# HelloLED.net
KiCad netlist of a schematic drawn in EAGLE
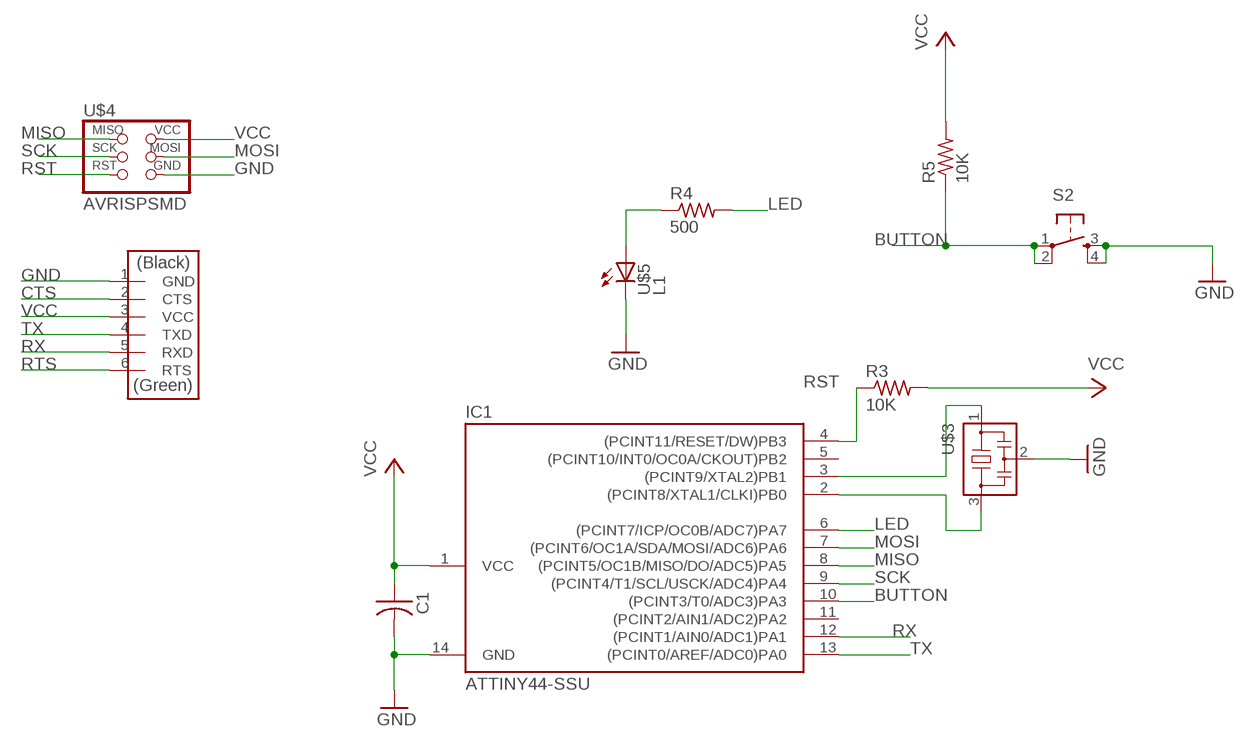
[diagram p0: schematic, sheet 1]

(export (version "E")
  (design (tool "Eeschema 10.0.6"))
  (components
    (comp (ref "C1")
      (value "CAP-US1206FAB")
      (footprint "eagle-import:C1206FAB")
      (libsource (lib "eagle-import") (part "CAP-US1206FAB"))
    )
    (comp (ref "IC1")
      (value "ATTINY44-SSU")
      (footprint "eagle-import:SOIC14")
      (libsource (lib "eagle-import") (part "ATTINY44-SSU"))
    )
    (comp (ref "R3")
      (value "10K")
      (footprint "eagle-import:R1206FAB")
      (fields (field (name "MF") "AVX CORPORATION") (field (name "MPN") "12106D226KAT2A"))
      (libsource (lib "eagle-import") (part "RES-US1206FAB"))
    )
    (comp (ref "R4")
      (value "500")
      (footprint "eagle-import:R1206FAB")
      (libsource (lib "eagle-import") (part "RES-US1206FAB"))
    )
    (comp (ref "R5")
      (value "10K")
      (footprint "eagle-import:R1206FAB")
      (fields (field (name "MF") "AVX CORPORATION") (field (name "MPN") "12106D226KAT2A"))
      (libsource (lib "eagle-import") (part "RES-US1206FAB"))
    )
    (comp (ref "S2")
      (value "6MM_SWITCH6MM_SWITCH")
      (footprint "eagle-import:6MM_SWITCH")
      (libsource (lib "eagle-import") (part "6MM_SWITCH6MM_SWITCH"))
    )
    (comp (ref "U$1")
      (value "FTDI-SMD-HEADER")
      (footprint "eagle-import:1X06SMD")
      (libsource (lib "eagle-import") (part "FTDI-SMD-HEADER"))
    )
    (comp (ref "U$3")
      (value "RESONATOR")
      (footprint "eagle-import:EFOBM")
      (libsource (lib "eagle-import") (part "RESONATOR"))
    )
    (comp (ref "U$4")
      (value "AVRISPSMD")
      (footprint "eagle-import:2X03SMD")
      (libsource (lib "eagle-import") (part "AVRISPSMD"))
    )
    (comp (ref "U$5")
      (value "L1")
      (footprint "eagle-import:LED1206FAB")
      (libsource (lib "eagle-import") (part "LEDFAB1206"))
    )
  )
  (nets
    (net (code "1") (name "/BUTTON") (class "Default")
      (node (ref "IC1") (pin "10") (pinfunction "(PCINT3/T0/ADC3)PA3_10") (pintype "bidirectional"))
      (node (ref "R5") (pin "1") (pinfunction "1_1") (pintype "passive"))
      (node (ref "S2") (pin "1") (pinfunction "P_1") (pintype "passive"))
      (node (ref "S2") (pin "2") (pinfunction "P1_2") (pintype "passive"))
    )
    (net (code "2") (name "/CTS") (class "Default")
      (node (ref "U$1") (pin "2") (pinfunction "CTS_2") (pintype "bidirectional"))
    )
    (net (code "3") (name "/LED") (class "Default")
      (node (ref "IC1") (pin "6") (pinfunction "(PCINT7/ICP/OC0B/ADC7)PA7_6") (pintype "bidirectional"))
      (node (ref "R4") (pin "2") (pinfunction "2_2") (pintype "passive"))
    )
    (net (code "4") (name "/MISO") (class "Default")
      (node (ref "IC1") (pin "8") (pinfunction "(PCINT5/OC1B/MISO/DO/ADC5)PA5_8") (pintype "bidirectional"))
      (node (ref "U$4") (pin "1") (pinfunction "MISO_1") (pintype "passive"))
    )
    (net (code "5") (name "/MOSI") (class "Default")
      (node (ref "IC1") (pin "7") (pinfunction "(PCINT6/OC1A/SDA/MOSI/ADC6)PA6_7") (pintype "bidirectional"))
      (node (ref "U$4") (pin "4") (pinfunction "MOSI_4") (pintype "passive"))
    )
    (net (code "6") (name "/RST") (class "Default")
      (node (ref "IC1") (pin "4") (pinfunction "(PCINT11/RESET/DW)PB3_4") (pintype "bidirectional"))
      (node (ref "R3") (pin "1") (pinfunction "1_1") (pintype "passive"))
      (node (ref "U$4") (pin "5") (pinfunction "RST_5") (pintype "passive"))
    )
    (net (code "7") (name "/RTS") (class "Default")
      (node (ref "U$1") (pin "6") (pinfunction "RTS_6") (pintype "bidirectional"))
    )
    (net (code "8") (name "/RX") (class "Default")
      (node (ref "IC1") (pin "12") (pinfunction "(PCINT1/AIN0/ADC1)PA1_12") (pintype "bidirectional"))
      (node (ref "U$1") (pin "5") (pinfunction "RXD_5") (pintype "bidirectional"))
    )
    (net (code "9") (name "/SCK") (class "Default")
      (node (ref "IC1") (pin "9") (pinfunction "(PCINT4/T1/SCL/USCK/ADC4)PA4_9") (pintype "bidirectional"))
      (node (ref "U$4") (pin "3") (pinfunction "SCK_3") (pintype "passive"))
    )
    (net (code "10") (name "/TX") (class "Default")
      (node (ref "IC1") (pin "13") (pinfunction "(PCINT0/AREF/ADC0)PA0_13") (pintype "bidirectional"))
      (node (ref "U$1") (pin "4") (pinfunction "TXD_4") (pintype "bidirectional"))
    )
    (net (code "11") (name "GND") (class "Default")
      (node (ref "C1") (pin "2") (pinfunction "2_2") (pintype "passive"))
      (node (ref "IC1") (pin "14") (pinfunction "GND_14") (pintype "power_in"))
      (node (ref "S2") (pin "3") (pinfunction "S_3") (pintype "passive"))
      (node (ref "S2") (pin "4") (pinfunction "S1_4") (pintype "passive"))
      (node (ref "U$1") (pin "1") (pinfunction "GND_1") (pintype "bidirectional"))
      (node (ref "U$3") (pin "2") (pinfunction "2_2") (pintype "passive"))
      (node (ref "U$4") (pin "6") (pinfunction "GND_6") (pintype "passive"))
      (node (ref "U$5") (pin "2") (pinfunction "C_2") (pintype "passive"))
    )
    (net (code "12") (name "Net-(IC1-(PCINT8{slash}XTAL1{slash}CLKI)PB0)") (class "Default")
      (node (ref "IC1") (pin "2") (pinfunction "(PCINT8/XTAL1/CLKI)PB0_2") (pintype "bidirectional"))
      (node (ref "U$3") (pin "3") (pinfunction "3_3") (pintype "passive"))
    )
    (net (code "13") (name "Net-(IC1-(PCINT9{slash}XTAL2)PB1)") (class "Default")
      (node (ref "IC1") (pin "3") (pinfunction "(PCINT9/XTAL2)PB1_3") (pintype "bidirectional"))
      (node (ref "U$3") (pin "1") (pinfunction "1_1") (pintype "passive"))
    )
    (net (code "14") (name "Net-(U$5-A)") (class "Default")
      (node (ref "R4") (pin "1") (pinfunction "1_1") (pintype "passive"))
      (node (ref "U$5") (pin "1") (pinfunction "A_1") (pintype "passive"))
    )
    (net (code "15") (name "VCC") (class "Default")
      (node (ref "C1") (pin "1") (pinfunction "1_1") (pintype "passive"))
      (node (ref "IC1") (pin "1") (pinfunction "VCC_1") (pintype "power_in"))
      (node (ref "R3") (pin "2") (pinfunction "2_2") (pintype "passive"))
      (node (ref "R5") (pin "2") (pinfunction "2_2") (pintype "passive"))
      (node (ref "U$1") (pin "3") (pinfunction "VCC_3") (pintype "bidirectional"))
      (node (ref "U$4") (pin "2") (pinfunction "VCC_2") (pintype "passive"))
    )
    (net (code "16") (name "unconnected-(IC1-(PCINT2{slash}AIN1{slash}ADC2)PA2-Pad11)") (class "Default")
      (node (ref "IC1") (pin "11") (pinfunction "(PCINT2/AIN1/ADC2)PA2_11") (pintype "bidirectional"))
    )
    (net (code "17") (name "unconnected-(IC1-(PCINT10{slash}INT0{slash}OC0A{slash}CKOUT)PB2-Pad5)") (class "Default")
      (node (ref "IC1") (pin "5") (pinfunction "(PCINT10/INT0/OC0A/CKOUT)PB2_5") (pintype "bidirectional"))
    )
  )
)
